# YQYtest.net
KiCad netlist of a schematic drawn in Altium Designer
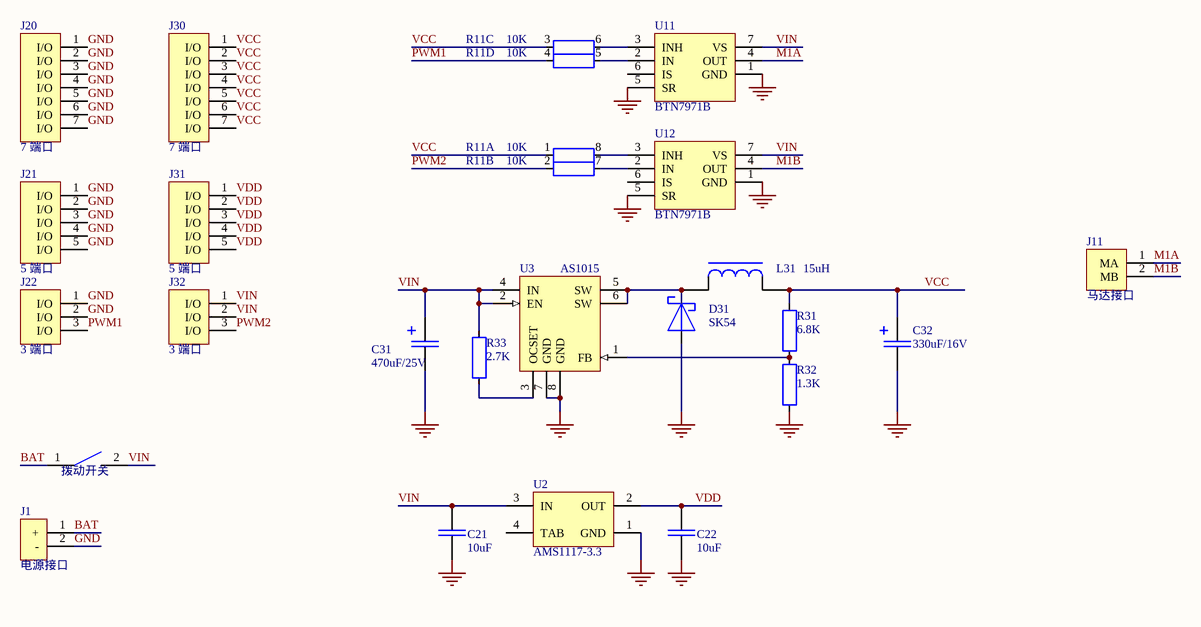
[diagram p0: YQYtest.SchDoc]

(export (version "E")
  (design (tool "Eeschema 10.0.6"))
  (components
    (comp (ref "C21") (value "10uF") (footprint "0805") (libsource (lib "RC") (part "C")))
    (comp (ref "C22") (value "10uF") (footprint "0805") (libsource (lib "RC") (part "C")))
    (comp (ref "C31") (value "470uF/25V") (footprint "CAPPR0.19") (libsource (lib "RC") (part "C+")))
    (comp (ref "C32") (value "330uF/16V") (footprint "CAPPR0.19") (libsource (lib "RC") (part "C+")))
    (comp (ref "D31") (value "SK54") (footprint "SMC/DO-214AB") (libsource (lib "RC") (part "D")))
    (comp (ref "J1") (value "电源接口") (footprint "DC12V") (libsource (lib "RC") (part "电源接口")))
    (comp (ref "J11") (value "马达接口") (footprint "MOTOR-W") (libsource (lib "RC") (part "马达接口")))
    (comp (ref "J20") (value "7 端口") (footprint "SIP7") (libsource (lib "RC") (part "7 端口")))
    (comp (ref "J21") (value "5 端口") (footprint "SIP5") (libsource (lib "RC") (part "5 端口")))
    (comp (ref "J22") (value "3 端口") (footprint "SIP3") (libsource (lib "RC") (part "3 端口")))
    (comp (ref "J30") (value "7 端口") (footprint "SIP7") (libsource (lib "RC") (part "7 端口")))
    (comp (ref "J31") (value "5 端口") (footprint "SIP5") (libsource (lib "RC") (part "5 端口")))
    (comp (ref "J32") (value "3 端口") (footprint "SIP3") (libsource (lib "RC") (part "3 端口")))
    (comp (ref "L31") (value "15uH") (footprint "4040电感") (libsource (lib "RC") (part "L")))
    (comp (ref "R11")
      (value "10K")
      (footprint "PZ-4")
      (description "Isolated Resistor Network - Parts")
      (libsource (lib "RC") (part "Res Pack"))
    )
    (comp (ref "R31") (value "6.8K") (footprint "0805") (libsource (lib "RC") (part "R")))
    (comp (ref "R32") (value "1.3K") (footprint "0805") (libsource (lib "RC") (part "R")))
    (comp (ref "R33") (value "2.7K") (footprint "0805") (libsource (lib "RC") (part "R")))
    (comp (ref "U2")
      (value "AMS1117-3.3")
      (footprint "MP04A_M")
      (description "800mA Low-Dropout Linear Regulator")
      (fields
        (field (name "PARTNUMBER") "LM1117MP-3.3")
        (field (name "MANUFACTURER") "National Semiconductor")
        (field (name "PUBLISHER") "Altium Limited")
      )
      (libsource (lib "RC") (part "LM1117MP-3.3"))
    )
    (comp (ref "U3") (value "AS1015") (footprint "SOP8_M") (libsource (lib "RC") (part "AS1015")))
    (comp (ref "U11") (value "BTN7971B") (footprint "TO263-7-1") (libsource (lib "RC") (part "BTN7971B")))
    (comp (ref "U12") (value "BTN7971B") (footprint "TO263-7-1") (libsource (lib "RC") (part "BTN7971B")))
    (comp (ref "拨动开关")
      (value "开关")
      (footprint "5A120V开关")
      (fields (field (name "PUBLISHER") "Altium Limited"))
      (libsource (lib "RC") (part "开关"))
    )
  )
  (nets
    (net (code "1") (name "/BAT") (class "Default")
      (node (ref "J1") (pin "1") (pinfunction "+_1") (pintype "passive"))
      (node (ref "拨动开关") (pin "1") (pinfunction "1_1") (pintype "passive"))
    )
    (net (code "2") (name "/M1A") (class "Default")
      (node (ref "J11") (pin "1") (pinfunction "MA_1") (pintype "passive"))
      (node (ref "U11") (pin "4") (pinfunction "OUT_4") (pintype "passive"))
    )
    (net (code "3") (name "/M1B") (class "Default")
      (node (ref "J11") (pin "2") (pinfunction "MB_2") (pintype "passive"))
      (node (ref "U12") (pin "4") (pinfunction "OUT_4") (pintype "passive"))
    )
    (net (code "4") (name "/PWM1") (class "Default")
      (node (ref "J22") (pin "3") (pinfunction "I/O_3") (pintype "passive"))
      (node (ref "R11") (pin "4") (pinfunction "4_4") (pintype "passive"))
    )
    (net (code "5") (name "/PWM2") (class "Default")
      (node (ref "J32") (pin "3") (pinfunction "I/O_3") (pintype "passive"))
      (node (ref "R11") (pin "2") (pinfunction "2_2") (pintype "passive"))
    )
    (net (code "6") (name "/VCC") (class "Default")
      (node (ref "C32") (pin "1") (pinfunction "1_1") (pintype "passive"))
      (node (ref "J30") (pin "1") (pinfunction "I/O_1") (pintype "passive"))
      (node (ref "J30") (pin "2") (pinfunction "I/O_2") (pintype "passive"))
      (node (ref "J30") (pin "3") (pinfunction "I/O_3") (pintype "passive"))
      (node (ref "J30") (pin "4") (pinfunction "I/O_4") (pintype "passive"))
      (node (ref "J30") (pin "5") (pinfunction "I/O_5") (pintype "passive"))
      (node (ref "J30") (pin "6") (pinfunction "I/O_6") (pintype "passive"))
      (node (ref "J30") (pin "7") (pinfunction "I/O_7") (pintype "passive"))
      (node (ref "L31") (pin "2") (pinfunction "2_2") (pintype "passive"))
      (node (ref "R11") (pin "1") (pinfunction "1_1") (pintype "passive"))
      (node (ref "R11") (pin "3") (pinfunction "3_3") (pintype "passive"))
      (node (ref "R31") (pin "2") (pinfunction "2_2") (pintype "passive"))
    )
    (net (code "7") (name "/VDD") (class "Default")
      (node (ref "C22") (pin "1") (pinfunction "1_1") (pintype "passive"))
      (node (ref "J31") (pin "1") (pinfunction "I/O_1") (pintype "passive"))
      (node (ref "J31") (pin "2") (pinfunction "I/O_2") (pintype "passive"))
      (node (ref "J31") (pin "3") (pinfunction "I/O_3") (pintype "passive"))
      (node (ref "J31") (pin "4") (pinfunction "I/O_4") (pintype "passive"))
      (node (ref "J31") (pin "5") (pinfunction "I/O_5") (pintype "passive"))
      (node (ref "U2") (pin "2") (pinfunction "OUT_2") (pintype "power_in"))
    )
    (net (code "8") (name "/VIN") (class "Default")
      (node (ref "C21") (pin "1") (pinfunction "1_1") (pintype "passive"))
      (node (ref "C31") (pin "1") (pinfunction "1_1") (pintype "passive"))
      (node (ref "J32") (pin "1") (pinfunction "I/O_1") (pintype "passive"))
      (node (ref "J32") (pin "2") (pinfunction "I/O_2") (pintype "passive"))
      (node (ref "R33") (pin "2") (pinfunction "2_2") (pintype "passive"))
      (node (ref "U11") (pin "7") (pinfunction "VS_7") (pintype "passive"))
      (node (ref "U12") (pin "7") (pinfunction "VS_7") (pintype "passive"))
      (node (ref "U2") (pin "3") (pinfunction "IN_3") (pintype "power_in"))
      (node (ref "U3") (pin "2") (pinfunction "EN_2") (pintype "input"))
      (node (ref "U3") (pin "4") (pinfunction "IN_4") (pintype "power_in"))
      (node (ref "拨动开关") (pin "2") (pinfunction "2_2") (pintype "passive"))
    )
    (net (code "9") (name "GND") (class "Default")
      (node (ref "C21") (pin "2") (pinfunction "2_2") (pintype "passive"))
      (node (ref "C22") (pin "2") (pinfunction "2_2") (pintype "passive"))
      (node (ref "C31") (pin "2") (pinfunction "2_2") (pintype "passive"))
      (node (ref "C32") (pin "2") (pinfunction "2_2") (pintype "passive"))
      (node (ref "D31") (pin "1") (pinfunction "A_1") (pintype "passive"))
      (node (ref "J1") (pin "2") (pinfunction "-_2") (pintype "passive"))
      (node (ref "J20") (pin "1") (pinfunction "I/O_1") (pintype "passive"))
      (node (ref "J20") (pin "2") (pinfunction "I/O_2") (pintype "passive"))
      (node (ref "J20") (pin "3") (pinfunction "I/O_3") (pintype "passive"))
      (node (ref "J20") (pin "4") (pinfunction "I/O_4") (pintype "passive"))
      (node (ref "J20") (pin "5") (pinfunction "I/O_5") (pintype "passive"))
      (node (ref "J20") (pin "6") (pinfunction "I/O_6") (pintype "passive"))
      (node (ref "J20") (pin "7") (pinfunction "I/O_7") (pintype "passive"))
      (node (ref "J21") (pin "1") (pinfunction "I/O_1") (pintype "passive"))
      (node (ref "J21") (pin "2") (pinfunction "I/O_2") (pintype "passive"))
      (node (ref "J21") (pin "3") (pinfunction "I/O_3") (pintype "passive"))
      (node (ref "J21") (pin "4") (pinfunction "I/O_4") (pintype "passive"))
      (node (ref "J21") (pin "5") (pinfunction "I/O_5") (pintype "passive"))
      (node (ref "J22") (pin "1") (pinfunction "I/O_1") (pintype "passive"))
      (node (ref "J22") (pin "2") (pinfunction "I/O_2") (pintype "passive"))
      (node (ref "R32") (pin "1") (pinfunction "1_1") (pintype "passive"))
      (node (ref "U11") (pin "1") (pinfunction "GND_1") (pintype "passive"))
      (node (ref "U11") (pin "5") (pinfunction "SR_5") (pintype "passive"))
      (node (ref "U12") (pin "1") (pinfunction "GND_1") (pintype "passive"))
      (node (ref "U12") (pin "5") (pinfunction "SR_5") (pintype "passive"))
      (node (ref "U2") (pin "1") (pinfunction "GND_1") (pintype "power_in"))
      (node (ref "U3") (pin "7") (pinfunction "GND_7") (pintype "passive"))
      (node (ref "U3") (pin "8") (pinfunction "GND_8") (pintype "passive"))
    )
    (net (code "10") (name "Net-(D31-K)") (class "Default")
      (node (ref "D31") (pin "2") (pinfunction "K_2") (pintype "passive"))
      (node (ref "L31") (pin "1") (pinfunction "1_1") (pintype "passive"))
      (node (ref "U3") (pin "5") (pinfunction "SW_5") (pintype "power_in"))
      (node (ref "U3") (pin "6") (pinfunction "SW_6") (pintype "power_in"))
    )
    (net (code "11") (name "Net-(U3-FB)") (class "Default")
      (node (ref "R31") (pin "1") (pinfunction "1_1") (pintype "passive"))
      (node (ref "R32") (pin "2") (pinfunction "2_2") (pintype "passive"))
      (node (ref "U3") (pin "1") (pinfunction "FB_1") (pintype "input"))
    )
    (net (code "12") (name "Net-(U3-OCSET)") (class "Default")
      (node (ref "R33") (pin "1") (pinfunction "1_1") (pintype "passive"))
      (node (ref "U3") (pin "3") (pinfunction "OCSET_3") (pintype "power_in"))
    )
    (net (code "13") (name "Net-(U11-IN)") (class "Default")
      (node (ref "R11") (pin "5") (pinfunction "5_5") (pintype "passive"))
      (node (ref "U11") (pin "2") (pinfunction "IN_2") (pintype "passive"))
    )
    (net (code "14") (name "Net-(U11-INH)") (class "Default")
      (node (ref "R11") (pin "6") (pinfunction "6_6") (pintype "passive"))
      (node (ref "U11") (pin "3") (pinfunction "INH_3") (pintype "passive"))
    )
    (net (code "15") (name "Net-(U12-IN)") (class "Default")
      (node (ref "R11") (pin "7") (pinfunction "7_7") (pintype "passive"))
      (node (ref "U12") (pin "2") (pinfunction "IN_2") (pintype "passive"))
    )
    (net (code "16") (name "Net-(U12-INH)") (class "Default")
      (node (ref "R11") (pin "8") (pinfunction "8_8") (pintype "passive"))
      (node (ref "U12") (pin "3") (pinfunction "INH_3") (pintype "passive"))
    )
    (net (code "17") (name "unconnected-(U2-TAB-Pad4)") (class "Default")
      (node (ref "U2") (pin "4") (pinfunction "TAB_4") (pintype "power_in"))
    )
    (net (code "18") (name "unconnected-(U11-IS-Pad6)") (class "Default")
      (node (ref "U11") (pin "6") (pinfunction "IS_6") (pintype "passive"))
    )
    (net (code "19") (name "unconnected-(U12-IS-Pad6)") (class "Default")
      (node (ref "U12") (pin "6") (pinfunction "IS_6") (pintype "passive"))
    )
  )
)
